# Conector_Interfaz.net
KiCad netlist of a schematic drawn in Altium Designer
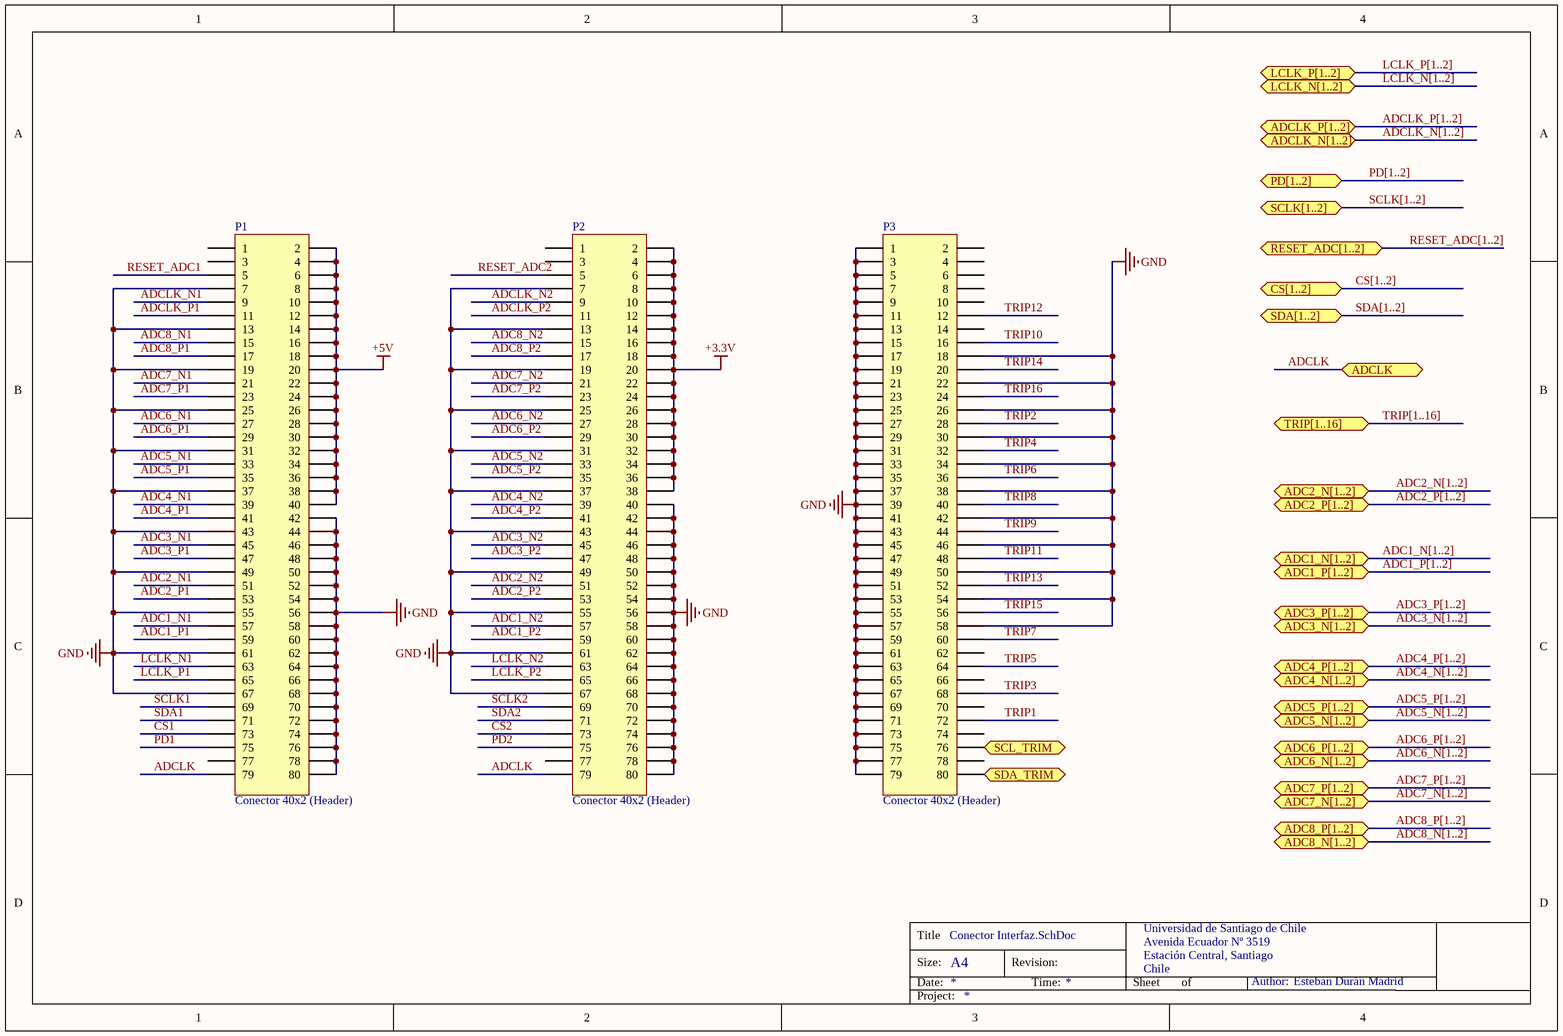
[diagram p0: Conector Interfaz.SchDoc]

(export (version "E")
  (design (tool "Eeschema 10.0.6"))
  (components
    (comp (ref "P1")
      (value "Conector 40x2 (Header)")
      (footprint "Conector 80 Pines Hembra")
      (description "CONN RCPT 80POS 0.5MM SMD")
      (fields (field (name "PUBLISHER") "Altium Limited"))
      (libsource (lib "Componentes_SOC") (part "Header 40X2 Hembra (Hirose)"))
    )
    (comp (ref "P2")
      (value "Conector 40x2 (Header)")
      (footprint "Conector 80 Pines Hembra")
      (description "CONN RCPT 80POS 0.5MM SMD")
      (fields (field (name "PUBLISHER") "Altium Limited"))
      (libsource (lib "Componentes_SOC") (part "Header 40X2 Hembra (Hirose)"))
    )
    (comp (ref "P3")
      (value "Conector 40x2 (Header)")
      (footprint "Conector 80 Pines Hembra")
      (description "CONN RCPT 80POS 0.5MM SMD")
      (fields (field (name "PUBLISHER") "Altium Limited"))
      (libsource (lib "Componentes_SOC") (part "Header 40X2 Hembra (Hirose)"))
    )
  )
  (nets
    (net (code "1") (name "+3.3V") (class "Default")
      (node (ref "P2") (pin "10") (pinfunction "10_10") (pintype "passive"))
      (node (ref "P2") (pin "12") (pinfunction "12_12") (pintype "passive"))
      (node (ref "P2") (pin "14") (pinfunction "14_14") (pintype "passive"))
      (node (ref "P2") (pin "16") (pinfunction "16_16") (pintype "passive"))
      (node (ref "P2") (pin "18") (pinfunction "18_18") (pintype "passive"))
      (node (ref "P2") (pin "2") (pinfunction "2_2") (pintype "passive"))
      (node (ref "P2") (pin "20") (pinfunction "20_20") (pintype "passive"))
      (node (ref "P2") (pin "22") (pinfunction "22_22") (pintype "passive"))
      (node (ref "P2") (pin "24") (pinfunction "24_24") (pintype "passive"))
      (node (ref "P2") (pin "26") (pinfunction "26_26") (pintype "passive"))
      (node (ref "P2") (pin "28") (pinfunction "28_28") (pintype "passive"))
      (node (ref "P2") (pin "30") (pinfunction "30_30") (pintype "passive"))
      (node (ref "P2") (pin "32") (pinfunction "32_32") (pintype "passive"))
      (node (ref "P2") (pin "34") (pinfunction "34_34") (pintype "passive"))
      (node (ref "P2") (pin "36") (pinfunction "36_36") (pintype "passive"))
      (node (ref "P2") (pin "38") (pinfunction "38_38") (pintype "passive"))
      (node (ref "P2") (pin "4") (pinfunction "4_4") (pintype "passive"))
      (node (ref "P2") (pin "6") (pinfunction "6_6") (pintype "passive"))
      (node (ref "P2") (pin "8") (pinfunction "8_8") (pintype "passive"))
    )
    (net (code "2") (name "+5V") (class "Default")
      (node (ref "P1") (pin "10") (pinfunction "10_10") (pintype "passive"))
      (node (ref "P1") (pin "12") (pinfunction "12_12") (pintype "passive"))
      (node (ref "P1") (pin "14") (pinfunction "14_14") (pintype "passive"))
      (node (ref "P1") (pin "16") (pinfunction "16_16") (pintype "passive"))
      (node (ref "P1") (pin "18") (pinfunction "18_18") (pintype "passive"))
      (node (ref "P1") (pin "2") (pinfunction "2_2") (pintype "passive"))
      (node (ref "P1") (pin "20") (pinfunction "20_20") (pintype "passive"))
      (node (ref "P1") (pin "22") (pinfunction "22_22") (pintype "passive"))
      (node (ref "P1") (pin "24") (pinfunction "24_24") (pintype "passive"))
      (node (ref "P1") (pin "26") (pinfunction "26_26") (pintype "passive"))
      (node (ref "P1") (pin "28") (pinfunction "28_28") (pintype "passive"))
      (node (ref "P1") (pin "30") (pinfunction "30_30") (pintype "passive"))
      (node (ref "P1") (pin "32") (pinfunction "32_32") (pintype "passive"))
      (node (ref "P1") (pin "34") (pinfunction "34_34") (pintype "passive"))
      (node (ref "P1") (pin "36") (pinfunction "36_36") (pintype "passive"))
      (node (ref "P1") (pin "38") (pinfunction "38_38") (pintype "passive"))
      (node (ref "P1") (pin "4") (pinfunction "4_4") (pintype "passive"))
      (node (ref "P1") (pin "40") (pinfunction "40_40") (pintype "passive"))
      (node (ref "P1") (pin "6") (pinfunction "6_6") (pintype "passive"))
      (node (ref "P1") (pin "8") (pinfunction "8_8") (pintype "passive"))
    )
    (net (code "3") (name "/ADC1_N1") (class "Default")
      (node (ref "P1") (pin "57") (pinfunction "57_57") (pintype "passive"))
    )
    (net (code "4") (name "/ADC1_N2") (class "Default")
      (node (ref "P2") (pin "57") (pinfunction "57_57") (pintype "passive"))
    )
    (net (code "6") (name "/ADC1_P1") (class "Default")
      (node (ref "P1") (pin "59") (pinfunction "59_59") (pintype "passive"))
    )
    (net (code "7") (name "/ADC1_P2") (class "Default")
      (node (ref "P2") (pin "59") (pinfunction "59_59") (pintype "passive"))
    )
    (net (code "9") (name "/ADC2_N1") (class "Default")
      (node (ref "P1") (pin "51") (pinfunction "51_51") (pintype "passive"))
    )
    (net (code "10") (name "/ADC2_N2") (class "Default")
      (node (ref "P2") (pin "51") (pinfunction "51_51") (pintype "passive"))
    )
    (net (code "12") (name "/ADC2_P1") (class "Default")
      (node (ref "P1") (pin "53") (pinfunction "53_53") (pintype "passive"))
    )
    (net (code "13") (name "/ADC2_P2") (class "Default")
      (node (ref "P2") (pin "53") (pinfunction "53_53") (pintype "passive"))
    )
    (net (code "15") (name "/ADC3_N1") (class "Default")
      (node (ref "P1") (pin "45") (pinfunction "45_45") (pintype "passive"))
    )
    (net (code "16") (name "/ADC3_N2") (class "Default")
      (node (ref "P2") (pin "45") (pinfunction "45_45") (pintype "passive"))
    )
    (net (code "18") (name "/ADC3_P1") (class "Default")
      (node (ref "P1") (pin "47") (pinfunction "47_47") (pintype "passive"))
    )
    (net (code "19") (name "/ADC3_P2") (class "Default")
      (node (ref "P2") (pin "47") (pinfunction "47_47") (pintype "passive"))
    )
    (net (code "21") (name "/ADC4_N1") (class "Default")
      (node (ref "P1") (pin "39") (pinfunction "39_39") (pintype "passive"))
    )
    (net (code "22") (name "/ADC4_N2") (class "Default")
      (node (ref "P2") (pin "39") (pinfunction "39_39") (pintype "passive"))
    )
    (net (code "24") (name "/ADC4_P1") (class "Default")
      (node (ref "P1") (pin "41") (pinfunction "41_41") (pintype "passive"))
    )
    (net (code "25") (name "/ADC4_P2") (class "Default")
      (node (ref "P2") (pin "41") (pinfunction "41_41") (pintype "passive"))
    )
    (net (code "27") (name "/ADC5_N1") (class "Default")
      (node (ref "P1") (pin "33") (pinfunction "33_33") (pintype "passive"))
    )
    (net (code "28") (name "/ADC5_N2") (class "Default")
      (node (ref "P2") (pin "33") (pinfunction "33_33") (pintype "passive"))
    )
    (net (code "30") (name "/ADC5_P1") (class "Default")
      (node (ref "P1") (pin "35") (pinfunction "35_35") (pintype "passive"))
    )
    (net (code "31") (name "/ADC5_P2") (class "Default")
      (node (ref "P2") (pin "35") (pinfunction "35_35") (pintype "passive"))
    )
    (net (code "33") (name "/ADC6_N1") (class "Default")
      (node (ref "P1") (pin "27") (pinfunction "27_27") (pintype "passive"))
    )
    (net (code "34") (name "/ADC6_N2") (class "Default")
      (node (ref "P2") (pin "27") (pinfunction "27_27") (pintype "passive"))
    )
    (net (code "36") (name "/ADC6_P1") (class "Default")
      (node (ref "P1") (pin "29") (pinfunction "29_29") (pintype "passive"))
    )
    (net (code "37") (name "/ADC6_P2") (class "Default")
      (node (ref "P2") (pin "29") (pinfunction "29_29") (pintype "passive"))
    )
    (net (code "39") (name "/ADC7_N1") (class "Default")
      (node (ref "P1") (pin "21") (pinfunction "21_21") (pintype "passive"))
    )
    (net (code "40") (name "/ADC7_N2") (class "Default")
      (node (ref "P2") (pin "21") (pinfunction "21_21") (pintype "passive"))
    )
    (net (code "42") (name "/ADC7_P1") (class "Default")
      (node (ref "P1") (pin "23") (pinfunction "23_23") (pintype "passive"))
    )
    (net (code "43") (name "/ADC7_P2") (class "Default")
      (node (ref "P2") (pin "23") (pinfunction "23_23") (pintype "passive"))
    )
    (net (code "45") (name "/ADC8_N1") (class "Default")
      (node (ref "P1") (pin "15") (pinfunction "15_15") (pintype "passive"))
    )
    (net (code "46") (name "/ADC8_N2") (class "Default")
      (node (ref "P2") (pin "15") (pinfunction "15_15") (pintype "passive"))
    )
    (net (code "48") (name "/ADC8_P1") (class "Default")
      (node (ref "P1") (pin "17") (pinfunction "17_17") (pintype "passive"))
    )
    (net (code "49") (name "/ADC8_P2") (class "Default")
      (node (ref "P2") (pin "17") (pinfunction "17_17") (pintype "passive"))
    )
    (net (code "51") (name "/ADCLK") (class "Default")
      (node (ref "P1") (pin "79") (pinfunction "79_79") (pintype "passive"))
      (node (ref "P2") (pin "79") (pinfunction "79_79") (pintype "passive"))
    )
    (net (code "52") (name "/ADCLK_N1") (class "Default")
      (node (ref "P1") (pin "9") (pinfunction "9_9") (pintype "passive"))
    )
    (net (code "53") (name "/ADCLK_N2") (class "Default")
      (node (ref "P2") (pin "9") (pinfunction "9_9") (pintype "passive"))
    )
    (net (code "55") (name "/ADCLK_P1") (class "Default")
      (node (ref "P1") (pin "11") (pinfunction "11_11") (pintype "passive"))
    )
    (net (code "56") (name "/ADCLK_P2") (class "Default")
      (node (ref "P2") (pin "11") (pinfunction "11_11") (pintype "passive"))
    )
    (net (code "58") (name "/CS1") (class "Default")
      (node (ref "P1") (pin "73") (pinfunction "73_73") (pintype "passive"))
    )
    (net (code "59") (name "/CS2") (class "Default")
      (node (ref "P2") (pin "73") (pinfunction "73_73") (pintype "passive"))
    )
    (net (code "61") (name "/LCLK_N1") (class "Default")
      (node (ref "P1") (pin "63") (pinfunction "63_63") (pintype "passive"))
    )
    (net (code "62") (name "/LCLK_N2") (class "Default")
      (node (ref "P2") (pin "63") (pinfunction "63_63") (pintype "passive"))
    )
    (net (code "64") (name "/LCLK_P1") (class "Default")
      (node (ref "P1") (pin "65") (pinfunction "65_65") (pintype "passive"))
    )
    (net (code "65") (name "/LCLK_P2") (class "Default")
      (node (ref "P2") (pin "65") (pinfunction "65_65") (pintype "passive"))
    )
    (net (code "67") (name "/PD1") (class "Default")
      (node (ref "P1") (pin "75") (pinfunction "75_75") (pintype "passive"))
    )
    (net (code "68") (name "/PD2") (class "Default")
      (node (ref "P2") (pin "75") (pinfunction "75_75") (pintype "passive"))
    )
    (net (code "70") (name "/RESET_ADC1") (class "Default")
      (node (ref "P1") (pin "5") (pinfunction "5_5") (pintype "passive"))
    )
    (net (code "71") (name "/RESET_ADC2") (class "Default")
      (node (ref "P2") (pin "5") (pinfunction "5_5") (pintype "passive"))
    )
    (net (code "73") (name "/SCLK1") (class "Default")
      (node (ref "P1") (pin "69") (pinfunction "69_69") (pintype "passive"))
    )
    (net (code "74") (name "/SCLK2") (class "Default")
      (node (ref "P2") (pin "69") (pinfunction "69_69") (pintype "passive"))
    )
    (net (code "76") (name "/SCL_TRIM") (class "Default")
      (node (ref "P3") (pin "76") (pinfunction "76_76") (pintype "passive"))
    )
    (net (code "77") (name "/SDA1") (class "Default")
      (node (ref "P1") (pin "71") (pinfunction "71_71") (pintype "passive"))
    )
    (net (code "78") (name "/SDA2") (class "Default")
      (node (ref "P2") (pin "71") (pinfunction "71_71") (pintype "passive"))
    )
    (net (code "80") (name "/SDA_TRIM") (class "Default")
      (node (ref "P3") (pin "80") (pinfunction "80_80") (pintype "passive"))
    )
    (net (code "81") (name "/TRIP1") (class "Default")
      (node (ref "P3") (pin "72") (pinfunction "72_72") (pintype "passive"))
    )
    (net (code "82") (name "/TRIP2") (class "Default")
      (node (ref "P3") (pin "28") (pinfunction "28_28") (pintype "passive"))
    )
    (net (code "83") (name "/TRIP3") (class "Default")
      (node (ref "P3") (pin "68") (pinfunction "68_68") (pintype "passive"))
    )
    (net (code "84") (name "/TRIP4") (class "Default")
      (node (ref "P3") (pin "32") (pinfunction "32_32") (pintype "passive"))
    )
    (net (code "85") (name "/TRIP5") (class "Default")
      (node (ref "P3") (pin "64") (pinfunction "64_64") (pintype "passive"))
    )
    (net (code "86") (name "/TRIP6") (class "Default")
      (node (ref "P3") (pin "36") (pinfunction "36_36") (pintype "passive"))
    )
    (net (code "87") (name "/TRIP7") (class "Default")
      (node (ref "P3") (pin "60") (pinfunction "60_60") (pintype "passive"))
    )
    (net (code "88") (name "/TRIP8") (class "Default")
      (node (ref "P3") (pin "40") (pinfunction "40_40") (pintype "passive"))
    )
    (net (code "89") (name "/TRIP9") (class "Default")
      (node (ref "P3") (pin "44") (pinfunction "44_44") (pintype "passive"))
    )
    (net (code "90") (name "/TRIP10") (class "Default")
      (node (ref "P3") (pin "16") (pinfunction "16_16") (pintype "passive"))
    )
    (net (code "91") (name "/TRIP11") (class "Default")
      (node (ref "P3") (pin "48") (pinfunction "48_48") (pintype "passive"))
    )
    (net (code "92") (name "/TRIP12") (class "Default")
      (node (ref "P3") (pin "12") (pinfunction "12_12") (pintype "passive"))
    )
    (net (code "93") (name "/TRIP13") (class "Default")
      (node (ref "P3") (pin "52") (pinfunction "52_52") (pintype "passive"))
    )
    (net (code "94") (name "/TRIP14") (class "Default")
      (node (ref "P3") (pin "20") (pinfunction "20_20") (pintype "passive"))
    )
    (net (code "95") (name "/TRIP15") (class "Default")
      (node (ref "P3") (pin "56") (pinfunction "56_56") (pintype "passive"))
    )
    (net (code "96") (name "/TRIP16") (class "Default")
      (node (ref "P3") (pin "24") (pinfunction "24_24") (pintype "passive"))
    )
    (net (code "98") (name "GND") (class "Default")
      (node (ref "P1") (pin "13") (pinfunction "13_13") (pintype "passive"))
      (node (ref "P1") (pin "19") (pinfunction "19_19") (pintype "passive"))
      (node (ref "P1") (pin "25") (pinfunction "25_25") (pintype "passive"))
      (node (ref "P1") (pin "31") (pinfunction "31_31") (pintype "passive"))
      (node (ref "P1") (pin "37") (pinfunction "37_37") (pintype "passive"))
      (node (ref "P1") (pin "42") (pinfunction "42_42") (pintype "passive"))
      (node (ref "P1") (pin "43") (pinfunction "43_43") (pintype "passive"))
      (node (ref "P1") (pin "44") (pinfunction "44_44") (pintype "passive"))
      (node (ref "P1") (pin "46") (pinfunction "46_46") (pintype "passive"))
      (node (ref "P1") (pin "48") (pinfunction "48_48") (pintype "passive"))
      (node (ref "P1") (pin "49") (pinfunction "49_49") (pintype "passive"))
      (node (ref "P1") (pin "50") (pinfunction "50_50") (pintype "passive"))
      (node (ref "P1") (pin "52") (pinfunction "52_52") (pintype "passive"))
      (node (ref "P1") (pin "54") (pinfunction "54_54") (pintype "passive"))
      (node (ref "P1") (pin "55") (pinfunction "55_55") (pintype "passive"))
      (node (ref "P1") (pin "56") (pinfunction "56_56") (pintype "passive"))
      (node (ref "P1") (pin "58") (pinfunction "58_58") (pintype "passive"))
      (node (ref "P1") (pin "60") (pinfunction "60_60") (pintype "passive"))
      (node (ref "P1") (pin "61") (pinfunction "61_61") (pintype "passive"))
      (node (ref "P1") (pin "62") (pinfunction "62_62") (pintype "passive"))
      (node (ref "P1") (pin "64") (pinfunction "64_64") (pintype "passive"))
      (node (ref "P1") (pin "66") (pinfunction "66_66") (pintype "passive"))
      (node (ref "P1") (pin "67") (pinfunction "67_67") (pintype "passive"))
      (node (ref "P1") (pin "68") (pinfunction "68_68") (pintype "passive"))
      (node (ref "P1") (pin "7") (pinfunction "7_7") (pintype "passive"))
      (node (ref "P1") (pin "70") (pinfunction "70_70") (pintype "passive"))
      (node (ref "P1") (pin "72") (pinfunction "72_72") (pintype "passive"))
      (node (ref "P1") (pin "74") (pinfunction "74_74") (pintype "passive"))
      (node (ref "P1") (pin "76") (pinfunction "76_76") (pintype "passive"))
      (node (ref "P1") (pin "78") (pinfunction "78_78") (pintype "passive"))
      (node (ref "P1") (pin "80") (pinfunction "80_80") (pintype "passive"))
      (node (ref "P2") (pin "13") (pinfunction "13_13") (pintype "passive"))
      (node (ref "P2") (pin "19") (pinfunction "19_19") (pintype "passive"))
      (node (ref "P2") (pin "25") (pinfunction "25_25") (pintype "passive"))
      (node (ref "P2") (pin "31") (pinfunction "31_31") (pintype "passive"))
      (node (ref "P2") (pin "37") (pinfunction "37_37") (pintype "passive"))
      (node (ref "P2") (pin "40") (pinfunction "40_40") (pintype "passive"))
      (node (ref "P2") (pin "42") (pinfunction "42_42") (pintype "passive"))
      (node (ref "P2") (pin "43") (pinfunction "43_43") (pintype "passive"))
      (node (ref "P2") (pin "44") (pinfunction "44_44") (pintype "passive"))
      (node (ref "P2") (pin "46") (pinfunction "46_46") (pintype "passive"))
      (node (ref "P2") (pin "48") (pinfunction "48_48") (pintype "passive"))
      (node (ref "P2") (pin "49") (pinfunction "49_49") (pintype "passive"))
      (node (ref "P2") (pin "50") (pinfunction "50_50") (pintype "passive"))
      (node (ref "P2") (pin "52") (pinfunction "52_52") (pintype "passive"))
      (node (ref "P2") (pin "54") (pinfunction "54_54") (pintype "passive"))
      (node (ref "P2") (pin "55") (pinfunction "55_55") (pintype "passive"))
      (node (ref "P2") (pin "56") (pinfunction "56_56") (pintype "passive"))
      (node (ref "P2") (pin "58") (pinfunction "58_58") (pintype "passive"))
      (node (ref "P2") (pin "60") (pinfunction "60_60") (pintype "passive"))
      (node (ref "P2") (pin "61") (pinfunction "61_61") (pintype "passive"))
      (node (ref "P2") (pin "62") (pinfunction "62_62") (pintype "passive"))
      (node (ref "P2") (pin "64") (pinfunction "64_64") (pintype "passive"))
      (node (ref "P2") (pin "66") (pinfunction "66_66") (pintype "passive"))
      (node (ref "P2") (pin "67") (pinfunction "67_67") (pintype "passive"))
      (node (ref "P2") (pin "68") (pinfunction "68_68") (pintype "passive"))
      (node (ref "P2") (pin "7") (pinfunction "7_7") (pintype "passive"))
      (node (ref "P2") (pin "70") (pinfunction "70_70") (pintype "passive"))
      (node (ref "P2") (pin "72") (pinfunction "72_72") (pintype "passive"))
      (node (ref "P2") (pin "74") (pinfunction "74_74") (pintype "passive"))
      (node (ref "P2") (pin "76") (pinfunction "76_76") (pintype "passive"))
      (node (ref "P2") (pin "78") (pinfunction "78_78") (pintype "passive"))
      (node (ref "P2") (pin "80") (pinfunction "80_80") (pintype "passive"))
      (node (ref "P3") (pin "1") (pinfunction "1_1") (pintype "passive"))
      (node (ref "P3") (pin "11") (pinfunction "11_11") (pintype "passive"))
      (node (ref "P3") (pin "13") (pinfunction "13_13") (pintype "passive"))
      (node (ref "P3") (pin "15") (pinfunction "15_15") (pintype "passive"))
      (node (ref "P3") (pin "17") (pinfunction "17_17") (pintype "passive"))
      (node (ref "P3") (pin "18") (pinfunction "18_18") (pintype "passive"))
      (node (ref "P3") (pin "19") (pinfunction "19_19") (pintype "passive"))
      (node (ref "P3") (pin "21") (pinfunction "21_21") (pintype "passive"))
      (node (ref "P3") (pin "22") (pinfunction "22_22") (pintype "passive"))
      (node (ref "P3") (pin "23") (pinfunction "23_23") (pintype "passive"))
      (node (ref "P3") (pin "25") (pinfunction "25_25") (pintype "passive"))
      (node (ref "P3") (pin "26") (pinfunction "26_26") (pintype "passive"))
      (node (ref "P3") (pin "27") (pinfunction "27_27") (pintype "passive"))
      (node (ref "P3") (pin "29") (pinfunction "29_29") (pintype "passive"))
      (node (ref "P3") (pin "3") (pinfunction "3_3") (pintype "passive"))
      (node (ref "P3") (pin "30") (pinfunction "30_30") (pintype "passive"))
      (node (ref "P3") (pin "31") (pinfunction "31_31") (pintype "passive"))
      (node (ref "P3") (pin "33") (pinfunction "33_33") (pintype "passive"))
      (node (ref "P3") (pin "34") (pinfunction "34_34") (pintype "passive"))
      (node (ref "P3") (pin "35") (pinfunction "35_35") (pintype "passive"))
      (node (ref "P3") (pin "37") (pinfunction "37_37") (pintype "passive"))
      (node (ref "P3") (pin "38") (pinfunction "38_38") (pintype "passive"))
      (node (ref "P3") (pin "39") (pinfunction "39_39") (pintype "passive"))
      (node (ref "P3") (pin "41") (pinfunction "41_41") (pintype "passive"))
      (node (ref "P3") (pin "42") (pinfunction "42_42") (pintype "passive"))
      (node (ref "P3") (pin "43") (pinfunction "43_43") (pintype "passive"))
      (node (ref "P3") (pin "45") (pinfunction "45_45") (pintype "passive"))
      (node (ref "P3") (pin "46") (pinfunction "46_46") (pintype "passive"))
      (node (ref "P3") (pin "47") (pinfunction "47_47") (pintype "passive"))
      (node (ref "P3") (pin "49") (pinfunction "49_49") (pintype "passive"))
      (node (ref "P3") (pin "5") (pinfunction "5_5") (pintype "passive"))
      (node (ref "P3") (pin "50") (pinfunction "50_50") (pintype "passive"))
      (node (ref "P3") (pin "51") (pinfunction "51_51") (pintype "passive"))
      (node (ref "P3") (pin "53") (pinfunction "53_53") (pintype "passive"))
      (node (ref "P3") (pin "54") (pinfunction "54_54") (pintype "passive"))
      (node (ref "P3") (pin "55") (pinfunction "55_55") (pintype "passive"))
      (node (ref "P3") (pin "57") (pinfunction "57_57") (pintype "passive"))
      (node (ref "P3") (pin "58") (pinfunction "58_58") (pintype "passive"))
      (node (ref "P3") (pin "59") (pinfunction "59_59") (pintype "passive"))
      (node (ref "P3") (pin "61") (pinfunction "61_61") (pintype "passive"))
      (node (ref "P3") (pin "63") (pinfunction "63_63") (pintype "passive"))
      (node (ref "P3") (pin "65") (pinfunction "65_65") (pintype "passive"))
      (node (ref "P3") (pin "67") (pinfunction "67_67") (pintype "passive"))
      (node (ref "P3") (pin "69") (pinfunction "69_69") (pintype "passive"))
      (node (ref "P3") (pin "7") (pinfunction "7_7") (pintype "passive"))
      (node (ref "P3") (pin "71") (pinfunction "71_71") (pintype "passive"))
      (node (ref "P3") (pin "73") (pinfunction "73_73") (pintype "passive"))
      (node (ref "P3") (pin "75") (pinfunction "75_75") (pintype "passive"))
      (node (ref "P3") (pin "77") (pinfunction "77_77") (pintype "passive"))
      (node (ref "P3") (pin "79") (pinfunction "79_79") (pintype "passive"))
      (node (ref "P3") (pin "9") (pinfunction "9_9") (pintype "passive"))
    )
    (net (code "99") (name "unconnected-(P1-Pad1)") (class "Default")
      (node (ref "P1") (pin "1") (pinfunction "1_1") (pintype "passive"))
    )
    (net (code "100") (name "unconnected-(P1-Pad3)") (class "Default")
      (node (ref "P1") (pin "3") (pinfunction "3_3") (pintype "passive"))
    )
    (net (code "101") (name "unconnected-(P1-Pad77)") (class "Default")
      (node (ref "P1") (pin "77") (pinfunction "77_77") (pintype "passive"))
    )
    (net (code "102") (name "unconnected-(P2-Pad1)") (class "Default")
      (node (ref "P2") (pin "1") (pinfunction "1_1") (pintype "passive"))
    )
    (net (code "103") (name "unconnected-(P2-Pad3)") (class "Default")
      (node (ref "P2") (pin "3") (pinfunction "3_3") (pintype "passive"))
    )
    (net (code "104") (name "unconnected-(P2-Pad77)") (class "Default")
      (node (ref "P2") (pin "77") (pinfunction "77_77") (pintype "passive"))
    )
    (net (code "105") (name "unconnected-(P3-Pad2)") (class "Default")
      (node (ref "P3") (pin "2") (pinfunction "2_2") (pintype "passive"))
    )
    (net (code "106") (name "unconnected-(P3-Pad4)") (class "Default")
      (node (ref "P3") (pin "4") (pinfunction "4_4") (pintype "passive"))
    )
    (net (code "107") (name "unconnected-(P3-Pad6)") (class "Default")
      (node (ref "P3") (pin "6") (pinfunction "6_6") (pintype "passive"))
    )
    (net (code "108") (name "unconnected-(P3-Pad8)") (class "Default")
      (node (ref "P3") (pin "8") (pinfunction "8_8") (pintype "passive"))
    )
    (net (code "109") (name "unconnected-(P3-Pad10)") (class "Default")
      (node (ref "P3") (pin "10") (pinfunction "10_10") (pintype "passive"))
    )
    (net (code "110") (name "unconnected-(P3-Pad14)") (class "Default")
      (node (ref "P3") (pin "14") (pinfunction "14_14") (pintype "passive"))
    )
    (net (code "111") (name "unconnected-(P3-Pad62)") (class "Default")
      (node (ref "P3") (pin "62") (pinfunction "62_62") (pintype "passive"))
    )
    (net (code "112") (name "unconnected-(P3-Pad66)") (class "Default")
      (node (ref "P3") (pin "66") (pinfunction "66_66") (pintype "passive"))
    )
    (net (code "113") (name "unconnected-(P3-Pad70)") (class "Default")
      (node (ref "P3") (pin "70") (pinfunction "70_70") (pintype "passive"))
    )
    (net (code "114") (name "unconnected-(P3-Pad74)") (class "Default")
      (node (ref "P3") (pin "74") (pinfunction "74_74") (pintype "passive"))
    )
    (net (code "115") (name "unconnected-(P3-Pad78)") (class "Default")
      (node (ref "P3") (pin "78") (pinfunction "78_78") (pintype "passive"))
    )
  )
)
